# Bop_it.net
KiCad netlist of a schematic drawn in Altium Designer
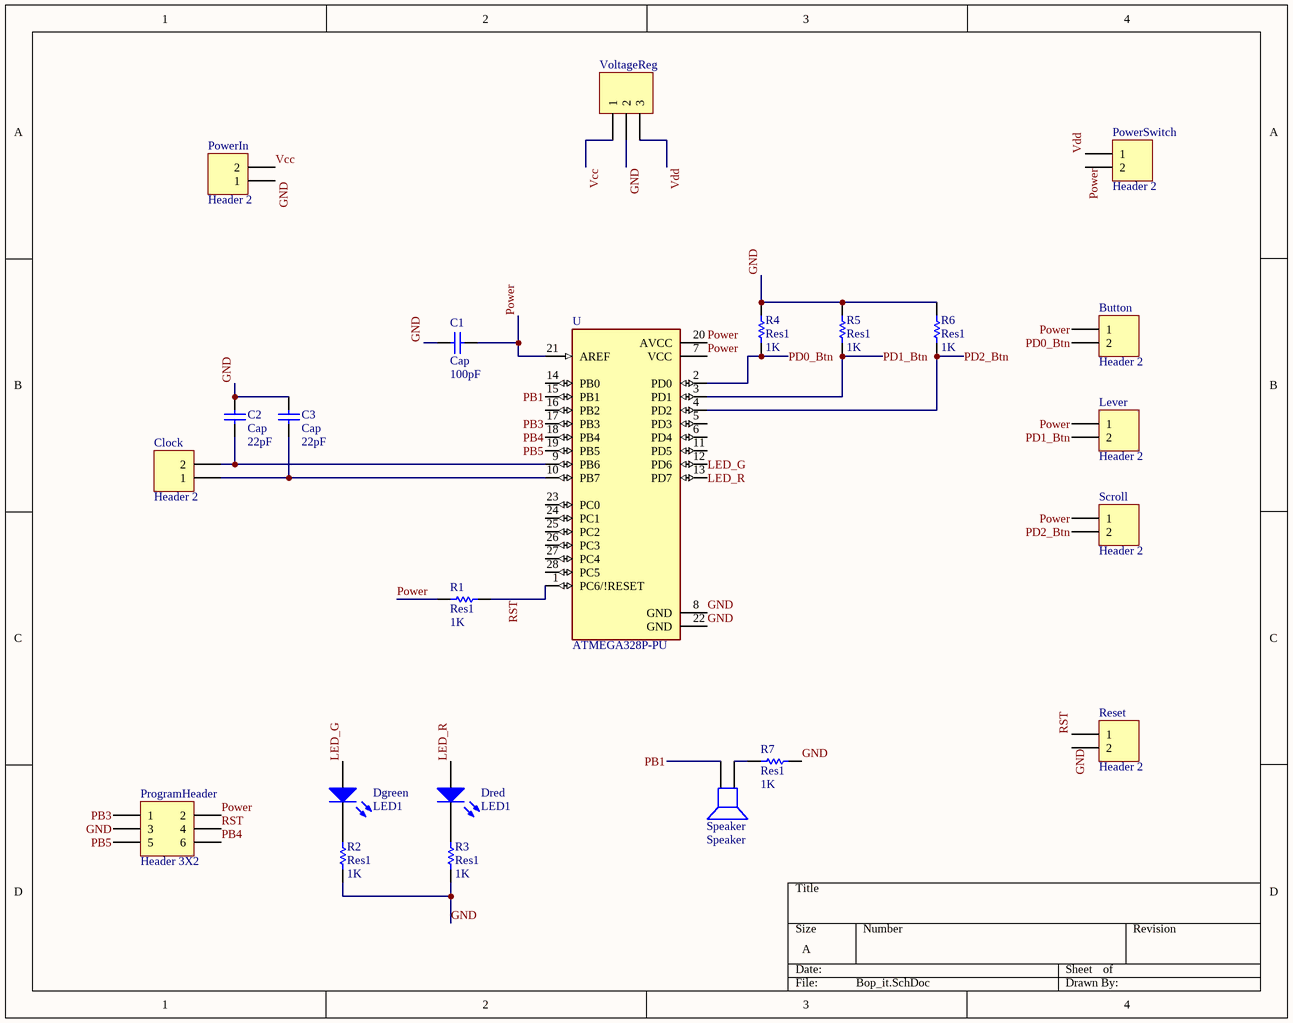
[diagram p0: Bop_it.SchDoc]

(export (version "E")
  (design (tool "Eeschema 10.0.6"))
  (components
    (comp (ref "Button")
      (value "Header 2")
      (footprint "HDR1X2")
      (description "Header, 2-Pin")
      (fields (field (name "PUBLISHER") "Altium Limited"))
      (libsource (lib "Miscellaneous Connectors") (part "Header 2"))
    )
    (comp (ref "C1")
      (value "Cap")
      (footprint "RAD-0.3")
      (description "Capacitor")
      (fields (field (name "ALTIUM_VALUE") "100pF") (field (name "PUBLISHER") "Altium Limited"))
      (libsource (lib "Miscellaneous Devices") (part "Cap"))
    )
    (comp (ref "C2")
      (value "Cap")
      (footprint "RAD-0.3")
      (description "Capacitor")
      (fields (field (name "ALTIUM_VALUE") "22pF") (field (name "PUBLISHER") "Altium Limited"))
      (libsource (lib "Miscellaneous Devices") (part "Cap"))
    )
    (comp (ref "C3")
      (value "Cap")
      (footprint "RAD-0.3")
      (description "Capacitor")
      (fields (field (name "ALTIUM_VALUE") "22pF") (field (name "PUBLISHER") "Altium Limited"))
      (libsource (lib "Miscellaneous Devices") (part "Cap"))
    )
    (comp (ref "Clock")
      (value "Header 2")
      (footprint "HDR1X2")
      (description "Header, 2-Pin")
      (fields (field (name "PUBLISHER") "Altium Limited"))
      (libsource (lib "") (part "Header 2_1"))
    )
    (comp (ref "Dgreen")
      (value "LED1")
      (footprint "LED-1")
      (description "Typical RED GaAs LED")
      (fields (field (name "PUBLISHER") "Altium Limited"))
      (libsource (lib "Miscellaneous Devices") (part "LED1"))
    )
    (comp (ref "Dred")
      (value "LED1")
      (footprint "LED-1")
      (description "Typical RED GaAs LED")
      (fields (field (name "PUBLISHER") "Altium Limited"))
      (libsource (lib "Miscellaneous Devices") (part "LED1"))
    )
    (comp (ref "Lever")
      (value "Header 2")
      (footprint "HDR1X2")
      (description "Header, 2-Pin")
      (fields (field (name "PUBLISHER") "Altium Limited"))
      (libsource (lib "Miscellaneous Connectors") (part "Header 2"))
    )
    (comp (ref "PowerIn")
      (value "Header 2")
      (footprint "HDR1X2")
      (description "Header, 2-Pin")
      (fields (field (name "PUBLISHER") "Altium Limited"))
      (libsource (lib "") (part "Header 2_1"))
    )
    (comp (ref "PowerSwitch")
      (value "Header 2")
      (footprint "HDR1X2")
      (description "Header, 2-Pin")
      (fields (field (name "PUBLISHER") "Altium Limited"))
      (libsource (lib "Miscellaneous Connectors") (part "Header 2"))
    )
    (comp (ref "ProgramHeader")
      (value "Header 3X2")
      (footprint "HDR2X3")
      (description "Header, 3-Pin, Dual row")
      (fields (field (name "PUBLISHER") "Altium Limited"))
      (libsource (lib "Miscellaneous Connectors") (part "Header 3X2"))
    )
    (comp (ref "R1")
      (value "Res1")
      (footprint "AXIAL-0.3")
      (description "Resistor")
      (fields (field (name "ALTIUM_VALUE") "1K") (field (name "PUBLISHER") "Altium Limited"))
      (libsource (lib "Miscellaneous Devices") (part "Res1"))
    )
    (comp (ref "R2")
      (value "Res1")
      (footprint "AXIAL-0.3")
      (description "Resistor")
      (fields (field (name "ALTIUM_VALUE") "1K") (field (name "PUBLISHER") "Altium Limited"))
      (libsource (lib "Miscellaneous Devices") (part "Res1"))
    )
    (comp (ref "R3")
      (value "Res1")
      (footprint "AXIAL-0.3")
      (description "Resistor")
      (fields (field (name "ALTIUM_VALUE") "1K") (field (name "PUBLISHER") "Altium Limited"))
      (libsource (lib "Miscellaneous Devices") (part "Res1"))
    )
    (comp (ref "R4")
      (value "Res1")
      (footprint "AXIAL-0.3")
      (description "Resistor")
      (fields (field (name "ALTIUM_VALUE") "1K") (field (name "PUBLISHER") "Altium Limited"))
      (libsource (lib "Miscellaneous Devices") (part "Res1"))
    )
    (comp (ref "R5")
      (value "Res1")
      (footprint "AXIAL-0.3")
      (description "Resistor")
      (fields (field (name "ALTIUM_VALUE") "1K") (field (name "PUBLISHER") "Altium Limited"))
      (libsource (lib "Miscellaneous Devices") (part "Res1"))
    )
    (comp (ref "R6")
      (value "Res1")
      (footprint "AXIAL-0.3")
      (description "Resistor")
      (fields (field (name "ALTIUM_VALUE") "1K") (field (name "PUBLISHER") "Altium Limited"))
      (libsource (lib "Miscellaneous Devices") (part "Res1"))
    )
    (comp (ref "R7")
      (value "Res1")
      (footprint "AXIAL-0.3")
      (description "Resistor")
      (fields (field (name "ALTIUM_VALUE") "1K") (field (name "PUBLISHER") "Altium Limited"))
      (libsource (lib "Miscellaneous Devices") (part "Res1"))
    )
    (comp (ref "Reset")
      (value "Header 2")
      (footprint "HDR1X2")
      (description "Header, 2-Pin")
      (fields (field (name "PUBLISHER") "Altium Limited"))
      (libsource (lib "Miscellaneous Connectors") (part "Header 2"))
    )
    (comp (ref "Scroll")
      (value "Header 2")
      (footprint "HDR1X2")
      (description "Header, 2-Pin")
      (fields (field (name "PUBLISHER") "Altium Limited"))
      (libsource (lib "Miscellaneous Connectors") (part "Header 2"))
    )
    (comp (ref "Speaker")
      (value "Speaker")
      (footprint "PIN2")
      (description "Loudspeaker")
      (fields (field (name "PUBLISHER") "Altium Limited"))
      (libsource (lib "Miscellaneous Devices") (part "Speaker"))
    )
    (comp (ref "U")
      (value "ATMEGA328P-PU")
      (footprint "DIP794W46P254L2967H457Q28B")
      (description "AVR AVRÂ® ATmega Microcontroller IC 8-Bit 20MHz 32KB _16K x 16_ FLASH 28-PDIP")
      (fields (field (name "MF") "Microchip"))
      (libsource (lib "ATMEGA328P-PU") (part "ATMEGA328P-PU"))
    )
    (comp (ref "VoltageReg")
      (value "~")
      (footprint "HDR1X3")
      (description "Header, 3-Pin")
      (fields (field (name "PUBLISHER") "Altium Limited"))
      (libsource (lib "Miscellaneous Connectors") (part "Header 3"))
    )
  )
  (nets
    (net (code "1") (name "/GND") (class "Default")
      (node (ref "C1") (pin "1") (pinfunction "1_1") (pintype "passive"))
      (node (ref "C2") (pin "2") (pinfunction "2_2") (pintype "passive"))
      (node (ref "C3") (pin "1") (pinfunction "1_1") (pintype "passive"))
      (node (ref "PowerIn") (pin "1") (pinfunction "1_1") (pintype "passive"))
      (node (ref "ProgramHeader") (pin "3") (pinfunction "3_3") (pintype "passive"))
      (node (ref "R2") (pin "2") (pinfunction "2_2") (pintype "passive"))
      (node (ref "R3") (pin "2") (pinfunction "2_2") (pintype "passive"))
      (node (ref "R4") (pin "1") (pinfunction "1_1") (pintype "passive"))
      (node (ref "R5") (pin "1") (pinfunction "1_1") (pintype "passive"))
      (node (ref "R6") (pin "1") (pinfunction "1_1") (pintype "passive"))
      (node (ref "R7") (pin "2") (pinfunction "2_2") (pintype "passive"))
      (node (ref "Reset") (pin "2") (pinfunction "2_2") (pintype "passive"))
      (node (ref "U") (pin "22") (pinfunction "GND_22") (pintype "power_in"))
      (node (ref "U") (pin "8") (pinfunction "GND_8") (pintype "power_in"))
      (node (ref "VoltageReg") (pin "2") (pinfunction "2_2") (pintype "passive"))
    )
    (net (code "2") (name "/LED_G") (class "Default")
      (node (ref "Dgreen") (pin "1") (pinfunction "A_1") (pintype "passive"))
      (node (ref "U") (pin "12") (pinfunction "PD6_12") (pintype "bidirectional"))
    )
    (net (code "3") (name "/LED_R") (class "Default")
      (node (ref "Dred") (pin "1") (pinfunction "A_1") (pintype "passive"))
      (node (ref "U") (pin "13") (pinfunction "PD7_13") (pintype "bidirectional"))
    )
    (net (code "4") (name "/PB1") (class "Default")
      (node (ref "Speaker") (pin "2") (pinfunction "2_2") (pintype "passive"))
      (node (ref "U") (pin "15") (pinfunction "PB1_15") (pintype "bidirectional"))
    )
    (net (code "5") (name "/PB3") (class "Default")
      (node (ref "ProgramHeader") (pin "1") (pinfunction "1_1") (pintype "passive"))
      (node (ref "U") (pin "17") (pinfunction "PB3_17") (pintype "bidirectional"))
    )
    (net (code "6") (name "/PB4") (class "Default")
      (node (ref "ProgramHeader") (pin "6") (pinfunction "6_6") (pintype "passive"))
      (node (ref "U") (pin "18") (pinfunction "PB4_18") (pintype "bidirectional"))
    )
    (net (code "7") (name "/PB5") (class "Default")
      (node (ref "ProgramHeader") (pin "5") (pinfunction "5_5") (pintype "passive"))
      (node (ref "U") (pin "19") (pinfunction "PB5_19") (pintype "bidirectional"))
    )
    (net (code "8") (name "/PD0_Btn") (class "Default")
      (node (ref "Button") (pin "2") (pinfunction "2_2") (pintype "passive"))
      (node (ref "R4") (pin "2") (pinfunction "2_2") (pintype "passive"))
      (node (ref "U") (pin "2") (pinfunction "PD0_2") (pintype "bidirectional"))
    )
    (net (code "9") (name "/PD1_Btn") (class "Default")
      (node (ref "Lever") (pin "2") (pinfunction "2_2") (pintype "passive"))
      (node (ref "R5") (pin "2") (pinfunction "2_2") (pintype "passive"))
      (node (ref "U") (pin "3") (pinfunction "PD1_3") (pintype "bidirectional"))
    )
    (net (code "10") (name "/PD2_Btn") (class "Default")
      (node (ref "R6") (pin "2") (pinfunction "2_2") (pintype "passive"))
      (node (ref "Scroll") (pin "2") (pinfunction "2_2") (pintype "passive"))
      (node (ref "U") (pin "4") (pinfunction "PD2_4") (pintype "bidirectional"))
    )
    (net (code "11") (name "/Power") (class "Default")
      (node (ref "Button") (pin "1") (pinfunction "1_1") (pintype "passive"))
      (node (ref "C1") (pin "2") (pinfunction "2_2") (pintype "passive"))
      (node (ref "Lever") (pin "1") (pinfunction "1_1") (pintype "passive"))
      (node (ref "PowerSwitch") (pin "2") (pinfunction "2_2") (pintype "passive"))
      (node (ref "ProgramHeader") (pin "2") (pinfunction "2_2") (pintype "passive"))
      (node (ref "R1") (pin "1") (pinfunction "1_1") (pintype "passive"))
      (node (ref "Scroll") (pin "1") (pinfunction "1_1") (pintype "passive"))
      (node (ref "U") (pin "20") (pinfunction "AVCC_20") (pintype "power_in"))
      (node (ref "U") (pin "21") (pinfunction "AREF_21") (pintype "input"))
      (node (ref "U") (pin "7") (pinfunction "VCC_7") (pintype "power_in"))
    )
    (net (code "12") (name "/RST") (class "Default")
      (node (ref "ProgramHeader") (pin "4") (pinfunction "4_4") (pintype "passive"))
      (node (ref "R1") (pin "2") (pinfunction "2_2") (pintype "passive"))
      (node (ref "Reset") (pin "1") (pinfunction "1_1") (pintype "passive"))
      (node (ref "U") (pin "1") (pinfunction "PC6/!RESET_1") (pintype "bidirectional"))
    )
    (net (code "13") (name "/Vcc") (class "Default")
      (node (ref "PowerIn") (pin "2") (pinfunction "2_2") (pintype "passive"))
      (node (ref "VoltageReg") (pin "1") (pinfunction "1_1") (pintype "passive"))
    )
    (net (code "14") (name "/Vdd") (class "Default")
      (node (ref "PowerSwitch") (pin "1") (pinfunction "1_1") (pintype "passive"))
      (node (ref "VoltageReg") (pin "3") (pinfunction "3_3") (pintype "passive"))
    )
    (net (code "15") (name "Net-(Dgreen-K)") (class "Default")
      (node (ref "Dgreen") (pin "2") (pinfunction "K_2") (pintype "passive"))
      (node (ref "R2") (pin "1") (pinfunction "1_1") (pintype "passive"))
    )
    (net (code "16") (name "Net-(Dred-K)") (class "Default")
      (node (ref "Dred") (pin "2") (pinfunction "K_2") (pintype "passive"))
      (node (ref "R3") (pin "1") (pinfunction "1_1") (pintype "passive"))
    )
    (net (code "17") (name "Net-(R7-Pad1)") (class "Default")
      (node (ref "R7") (pin "1") (pinfunction "1_1") (pintype "passive"))
      (node (ref "Speaker") (pin "1") (pinfunction "1_1") (pintype "passive"))
    )
    (net (code "18") (name "Net-(U-PB6)") (class "Default")
      (node (ref "C2") (pin "1") (pinfunction "1_1") (pintype "passive"))
      (node (ref "Clock") (pin "2") (pinfunction "2_2") (pintype "passive"))
      (node (ref "U") (pin "9") (pinfunction "PB6_9") (pintype "bidirectional"))
    )
    (net (code "19") (name "Net-(U-PB7)") (class "Default")
      (node (ref "C3") (pin "2") (pinfunction "2_2") (pintype "passive"))
      (node (ref "Clock") (pin "1") (pinfunction "1_1") (pintype "passive"))
      (node (ref "U") (pin "10") (pinfunction "PB7_10") (pintype "bidirectional"))
    )
    (net (code "20") (name "unconnected-(U-PB0-Pad14)") (class "Default")
      (node (ref "U") (pin "14") (pinfunction "PB0_14") (pintype "bidirectional"))
    )
    (net (code "21") (name "unconnected-(U-PB2-Pad16)") (class "Default")
      (node (ref "U") (pin "16") (pinfunction "PB2_16") (pintype "bidirectional"))
    )
    (net (code "22") (name "unconnected-(U-PC0-Pad23)") (class "Default")
      (node (ref "U") (pin "23") (pinfunction "PC0_23") (pintype "bidirectional"))
    )
    (net (code "23") (name "unconnected-(U-PC1-Pad24)") (class "Default")
      (node (ref "U") (pin "24") (pinfunction "PC1_24") (pintype "bidirectional"))
    )
    (net (code "24") (name "unconnected-(U-PC2-Pad25)") (class "Default")
      (node (ref "U") (pin "25") (pinfunction "PC2_25") (pintype "bidirectional"))
    )
    (net (code "25") (name "unconnected-(U-PC3-Pad26)") (class "Default")
      (node (ref "U") (pin "26") (pinfunction "PC3_26") (pintype "bidirectional"))
    )
    (net (code "26") (name "unconnected-(U-PC4-Pad27)") (class "Default")
      (node (ref "U") (pin "27") (pinfunction "PC4_27") (pintype "bidirectional"))
    )
    (net (code "27") (name "unconnected-(U-PC5-Pad28)") (class "Default")
      (node (ref "U") (pin "28") (pinfunction "PC5_28") (pintype "bidirectional"))
    )
    (net (code "28") (name "unconnected-(U-PD3-Pad5)") (class "Default")
      (node (ref "U") (pin "5") (pinfunction "PD3_5") (pintype "bidirectional"))
    )
    (net (code "29") (name "unconnected-(U-PD4-Pad6)") (class "Default")
      (node (ref "U") (pin "6") (pinfunction "PD4_6") (pintype "bidirectional"))
    )
    (net (code "30") (name "unconnected-(U-PD5-Pad11)") (class "Default")
      (node (ref "U") (pin "11") (pinfunction "PD5_11") (pintype "bidirectional"))
    )
  )
)
